# dermabragun_mentor_reno.net
KiCad netlist of a schematic drawn in EAGLE
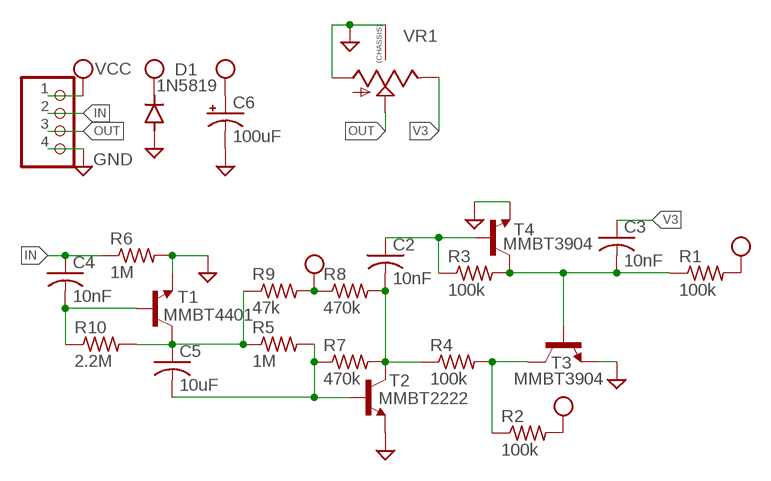
[diagram p0: schematic, sheet 1]

(export (version "E")
  (design (tool "Eeschema 10.0.6"))
  (components
    (comp (ref "C2")
      (value "10nF")
      (footprint "eagle-import:C0603")
      (libsource (lib "eagle-import") (part "C-USC0603"))
    )
    (comp (ref "C3")
      (value "10nF")
      (footprint "eagle-import:C0603")
      (libsource (lib "eagle-import") (part "C-USC0603"))
    )
    (comp (ref "C4")
      (value "10nF")
      (footprint "eagle-import:C0603")
      (libsource (lib "eagle-import") (part "C-USC0603"))
    )
    (comp (ref "C5")
      (value "10uF")
      (footprint "eagle-import:CAPC3216X135")
      (libsource (lib "eagle-import") (part "C-USCHIP-1206(3216-METRIC)_"))
    )
    (comp (ref "C6")
      (value "100uF")
      (footprint "eagle-import:CPOL-RADIAL-2.5MM-6.5MM")
      (libsource (lib "eagle-import") (part "100UF-POLAR-RADIAL-2.5MM-25V-20%"))
    )
    (comp (ref "D1")
      (value "1N5819")
      (footprint "eagle-import:SOD123")
      (libsource (lib "eagle-import") (part "DIODE-SOD123"))
    )
    (comp (ref "JP1")
      (value "PINHD-1X4")
      (footprint "eagle-import:1X04")
      (libsource (lib "eagle-import") (part "PINHD-1X4"))
    )
    (comp (ref "R1")
      (value "100k")
      (footprint "eagle-import:R0603")
      (libsource (lib "eagle-import") (part "R-US_R0603"))
    )
    (comp (ref "R2")
      (value "100k")
      (footprint "eagle-import:R0603")
      (libsource (lib "eagle-import") (part "R-US_R0603"))
    )
    (comp (ref "R3")
      (value "100k")
      (footprint "eagle-import:R0603")
      (libsource (lib "eagle-import") (part "R-US_R0603"))
    )
    (comp (ref "R4")
      (value "100k")
      (footprint "eagle-import:R0603")
      (libsource (lib "eagle-import") (part "R-US_R0603"))
    )
    (comp (ref "R5")
      (value "1M")
      (footprint "eagle-import:R0603")
      (libsource (lib "eagle-import") (part "R-US_R0603"))
    )
    (comp (ref "R6")
      (value "1M")
      (footprint "eagle-import:R0603")
      (libsource (lib "eagle-import") (part "R-US_R0603"))
    )
    (comp (ref "R7")
      (value "470k")
      (footprint "eagle-import:R0603")
      (libsource (lib "eagle-import") (part "R-US_R0603"))
    )
    (comp (ref "R8")
      (value "470k")
      (footprint "eagle-import:R0603")
      (libsource (lib "eagle-import") (part "R-US_R0603"))
    )
    (comp (ref "R9")
      (value "47k")
      (footprint "eagle-import:R0603")
      (libsource (lib "eagle-import") (part "R-US_R0603"))
    )
    (comp (ref "R10")
      (value "2.2M")
      (footprint "eagle-import:R0603")
      (libsource (lib "eagle-import") (part "R-US_R0603"))
    )
    (comp (ref "T1")
      (value "MMBT4401")
      (footprint "eagle-import:SOT23-BEC")
      (libsource (lib "eagle-import") (part "-NPN-SOT23-BECBC808"))
    )
    (comp (ref "T2")
      (value "MMBT2222")
      (footprint "eagle-import:SOT23-BEC")
      (libsource (lib "eagle-import") (part "-NPN-SOT23-BECMMBT2222ALT1"))
    )
    (comp (ref "T3")
      (value "MMBT3904")
      (footprint "eagle-import:SOT23-BEC")
      (libsource (lib "eagle-import") (part "-NPN-SOT23-BECMMBT3904LT1"))
    )
    (comp (ref "T4")
      (value "MMBT3904")
      (footprint "eagle-import:SOT23-BEC")
      (libsource (lib "eagle-import") (part "-NPN-SOT23-BECMMBT3904LT1"))
    )
    (comp (ref "VR1")
      (value "9MM_SNAP-IN_POT_CHASSIS")
      (footprint "eagle-import:9MM_SNAP-IN_POT")
      (libsource (lib "eagle-import") (part "9MM_SNAP-IN_POT_CHASSIS"))
    )
  )
  (nets
    (net (code "1") (name "GND") (class "Default")
      (node (ref "C6") (pin "2") (pinfunction "-_2") (pintype "passive"))
      (node (ref "D1") (pin "A") (pinfunction "A_A") (pintype "passive"))
      (node (ref "JP1") (pin "4") (pinfunction "4_4") (pintype "passive"))
      (node (ref "R6") (pin "2") (pinfunction "2_2") (pintype "passive"))
      (node (ref "T1") (pin "E") (pinfunction "E_E") (pintype "passive"))
      (node (ref "T2") (pin "E") (pinfunction "E_E") (pintype "passive"))
      (node (ref "T3") (pin "E") (pinfunction "E_E") (pintype "passive"))
      (node (ref "T4") (pin "E") (pinfunction "E_E") (pintype "passive"))
      (node (ref "VR1") (pin "1") (pinfunction "A_1") (pintype "passive"))
      (node (ref "VR1") (pin "CHASSIS1") (pinfunction "P$1_CHASSIS1") (pintype "passive"))
      (node (ref "VR1") (pin "CHASSIS2") (pinfunction "P$1_CHASSIS2") (pintype "passive"))
    )
    (net (code "2") (name "IN") (class "Default")
      (node (ref "C4") (pin "1") (pinfunction "1_1") (pintype "passive"))
      (node (ref "JP1") (pin "2") (pinfunction "2_2") (pintype "passive"))
      (node (ref "R6") (pin "1") (pinfunction "1_1") (pintype "passive"))
    )
    (net (code "3") (name "Net-(C2-Pad1)") (class "Default")
      (node (ref "C2") (pin "1") (pinfunction "1_1") (pintype "passive"))
      (node (ref "R3") (pin "1") (pinfunction "1_1") (pintype "passive"))
      (node (ref "T4") (pin "B") (pinfunction "B_B") (pintype "passive"))
    )
    (net (code "4") (name "Net-(C2-Pad2)") (class "Default")
      (node (ref "C2") (pin "2") (pinfunction "2_2") (pintype "passive"))
      (node (ref "R4") (pin "1") (pinfunction "1_1") (pintype "passive"))
      (node (ref "R7") (pin "2") (pinfunction "2_2") (pintype "passive"))
      (node (ref "R8") (pin "2") (pinfunction "2_2") (pintype "passive"))
      (node (ref "T2") (pin "C") (pinfunction "C_C") (pintype "passive"))
    )
    (net (code "5") (name "Net-(C3-Pad2)") (class "Default")
      (node (ref "C3") (pin "2") (pinfunction "2_2") (pintype "passive"))
      (node (ref "R1") (pin "1") (pinfunction "1_1") (pintype "passive"))
      (node (ref "R3") (pin "2") (pinfunction "2_2") (pintype "passive"))
      (node (ref "T3") (pin "B") (pinfunction "B_B") (pintype "passive"))
      (node (ref "T4") (pin "C") (pinfunction "C_C") (pintype "passive"))
    )
    (net (code "6") (name "Net-(C4-Pad2)") (class "Default")
      (node (ref "C4") (pin "2") (pinfunction "2_2") (pintype "passive"))
      (node (ref "R10") (pin "1") (pinfunction "1_1") (pintype "passive"))
      (node (ref "T1") (pin "B") (pinfunction "B_B") (pintype "passive"))
    )
    (net (code "7") (name "Net-(C5-Pad1)") (class "Default")
      (node (ref "C5") (pin "1") (pinfunction "1_1") (pintype "passive"))
      (node (ref "R10") (pin "2") (pinfunction "2_2") (pintype "passive"))
      (node (ref "R5") (pin "1") (pinfunction "1_1") (pintype "passive"))
      (node (ref "R9") (pin "1") (pinfunction "1_1") (pintype "passive"))
      (node (ref "T1") (pin "C") (pinfunction "C_C") (pintype "passive"))
    )
    (net (code "8") (name "Net-(C5-Pad2)") (class "Default")
      (node (ref "C5") (pin "2") (pinfunction "2_2") (pintype "passive"))
      (node (ref "R5") (pin "2") (pinfunction "2_2") (pintype "passive"))
      (node (ref "R7") (pin "1") (pinfunction "1_1") (pintype "passive"))
      (node (ref "T2") (pin "B") (pinfunction "B_B") (pintype "passive"))
    )
    (net (code "9") (name "Net-(R2-Pad1)") (class "Default")
      (node (ref "R2") (pin "1") (pinfunction "1_1") (pintype "passive"))
      (node (ref "R4") (pin "2") (pinfunction "2_2") (pintype "passive"))
      (node (ref "T3") (pin "C") (pinfunction "C_C") (pintype "passive"))
    )
    (net (code "10") (name "OUT") (class "Default")
      (node (ref "JP1") (pin "3") (pinfunction "3_3") (pintype "passive"))
      (node (ref "VR1") (pin "2") (pinfunction "S_2") (pintype "passive"))
    )
    (net (code "11") (name "V3") (class "Default")
      (node (ref "C3") (pin "1") (pinfunction "1_1") (pintype "passive"))
      (node (ref "VR1") (pin "3") (pinfunction "E_3") (pintype "passive"))
    )
    (net (code "12") (name "VCC") (class "Default")
      (node (ref "C6") (pin "1") (pinfunction "+_1") (pintype "passive"))
      (node (ref "D1") (pin "C") (pinfunction "C_C") (pintype "passive"))
      (node (ref "JP1") (pin "1") (pinfunction "1_1") (pintype "passive"))
      (node (ref "R1") (pin "2") (pinfunction "2_2") (pintype "passive"))
      (node (ref "R2") (pin "2") (pinfunction "2_2") (pintype "passive"))
      (node (ref "R8") (pin "1") (pinfunction "1_1") (pintype "passive"))
      (node (ref "R9") (pin "2") (pinfunction "2_2") (pintype "passive"))
    )
  )
)
